# SCH_Akira_Basic_2024-01-05.net
KiCad netlist of a schematic drawn in EasyEDA
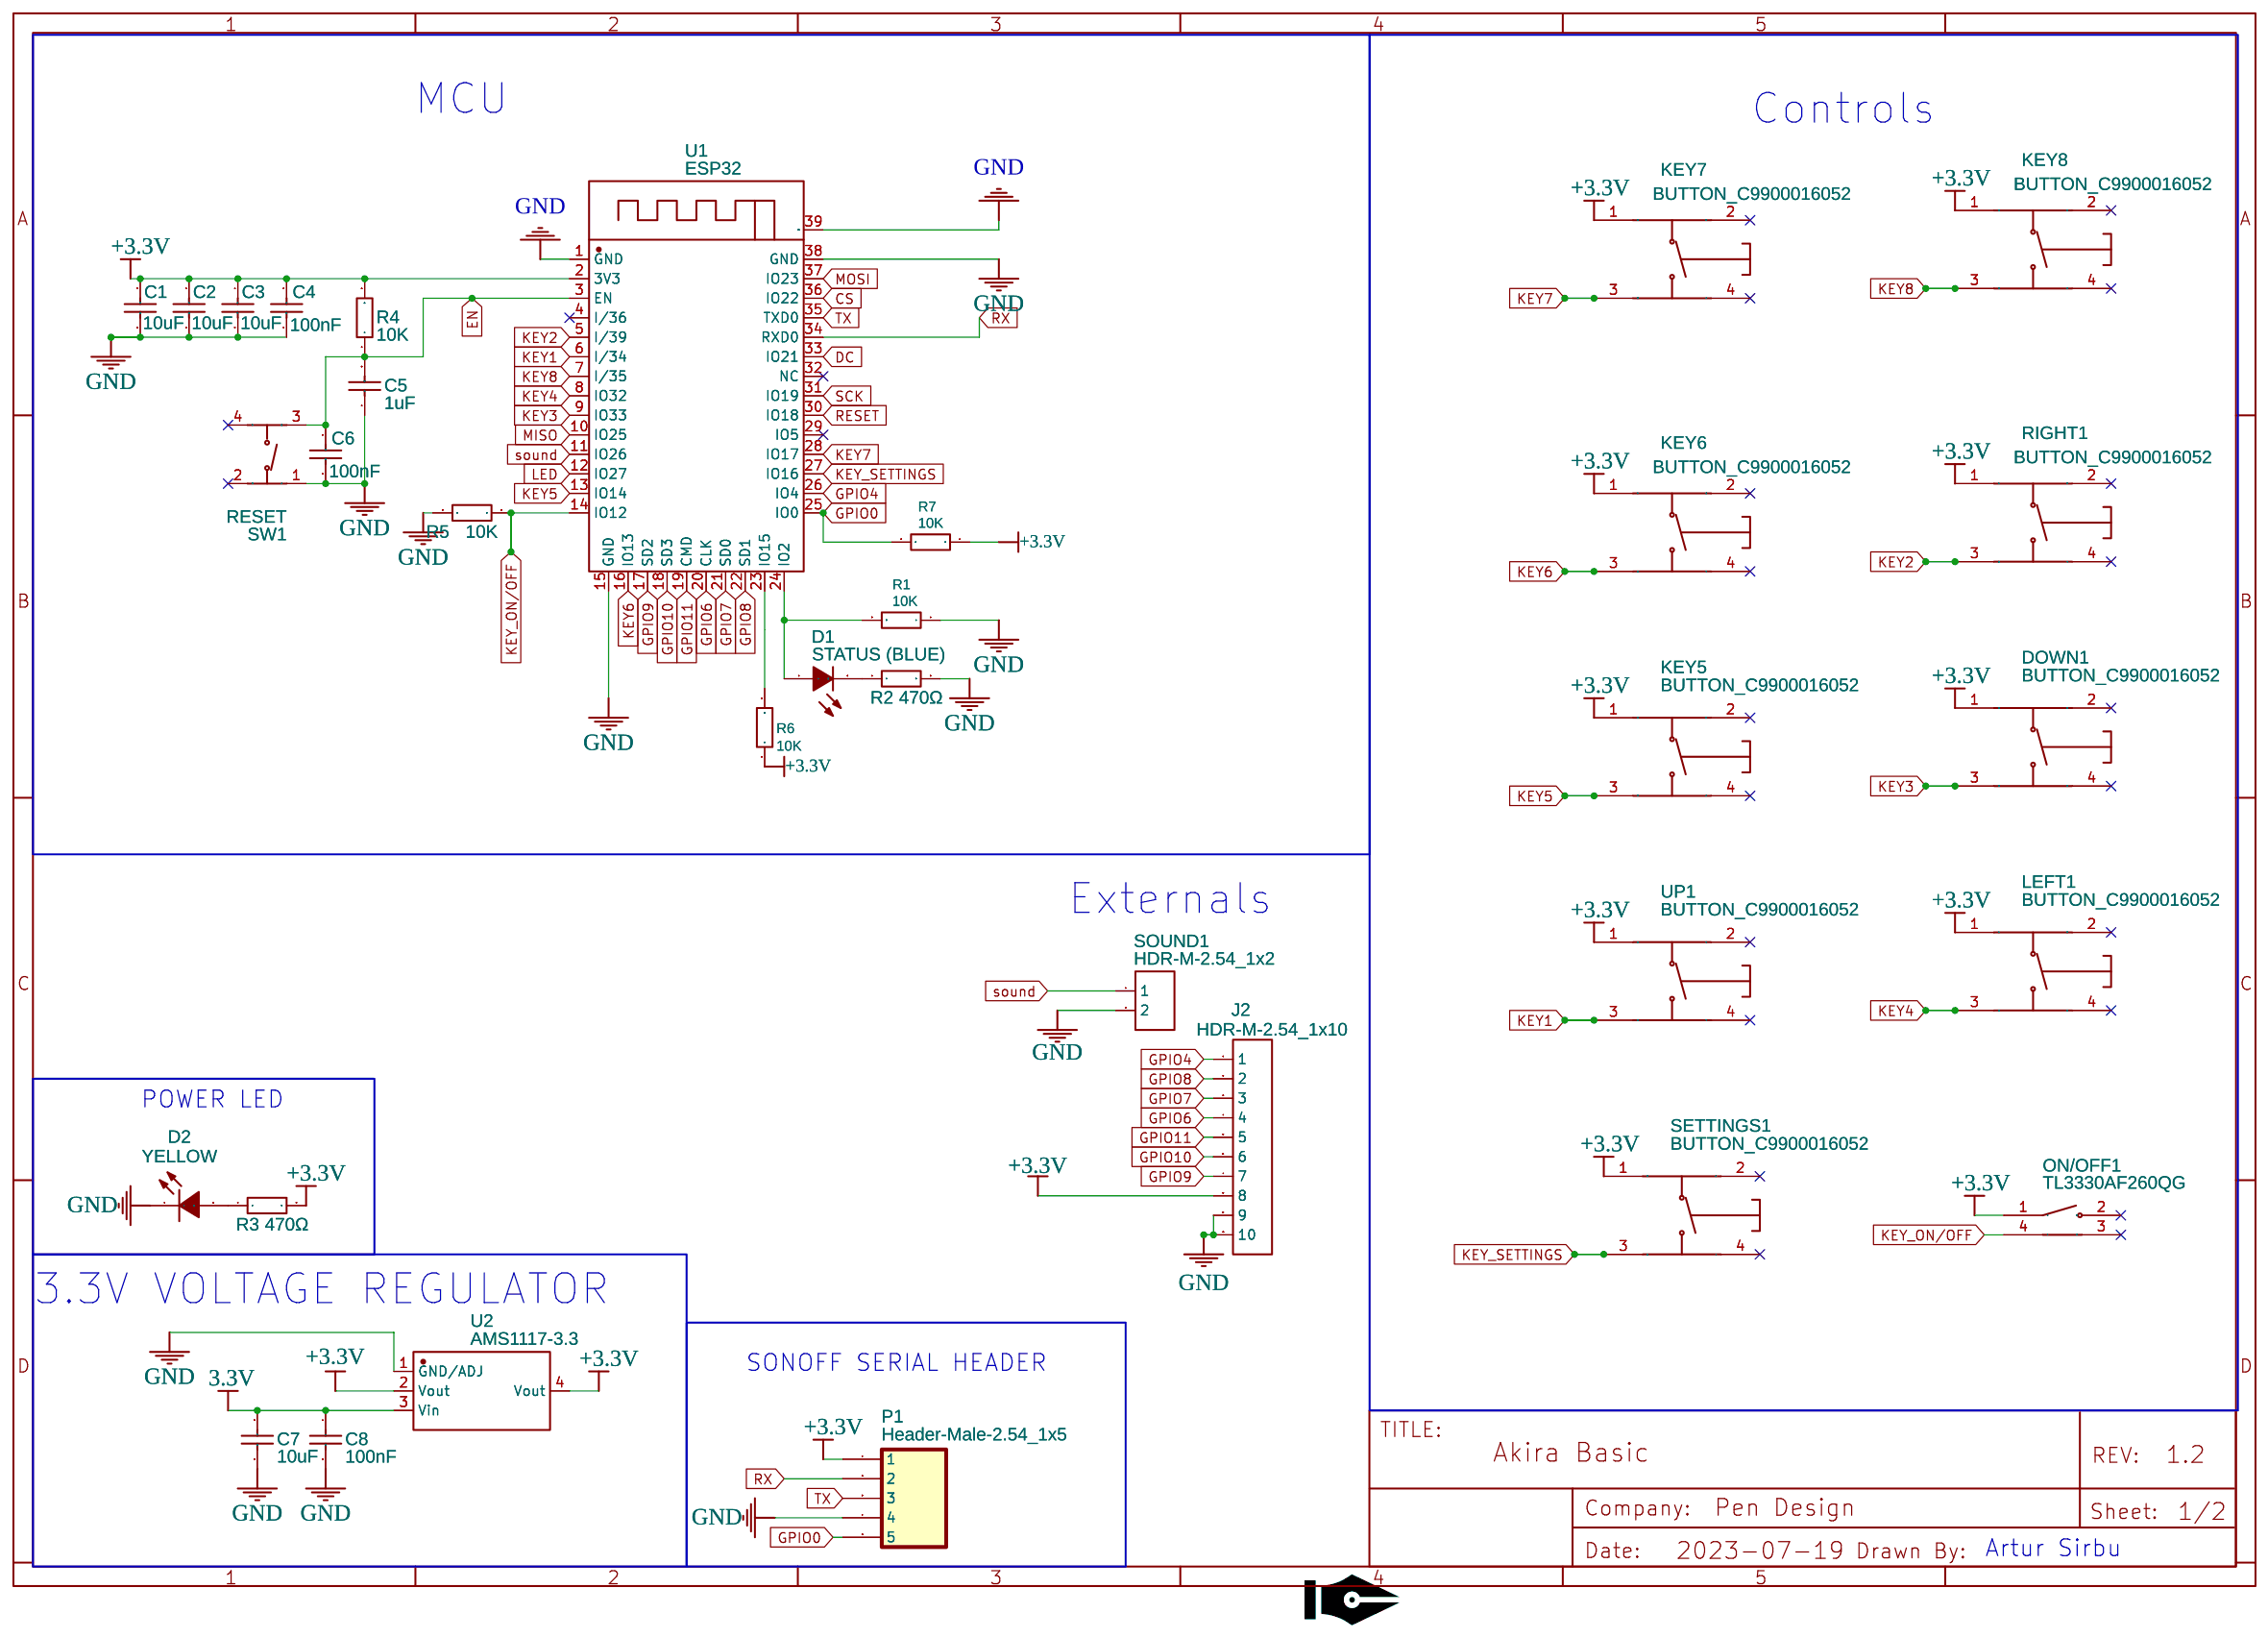
[diagram p0: Sheet_1]
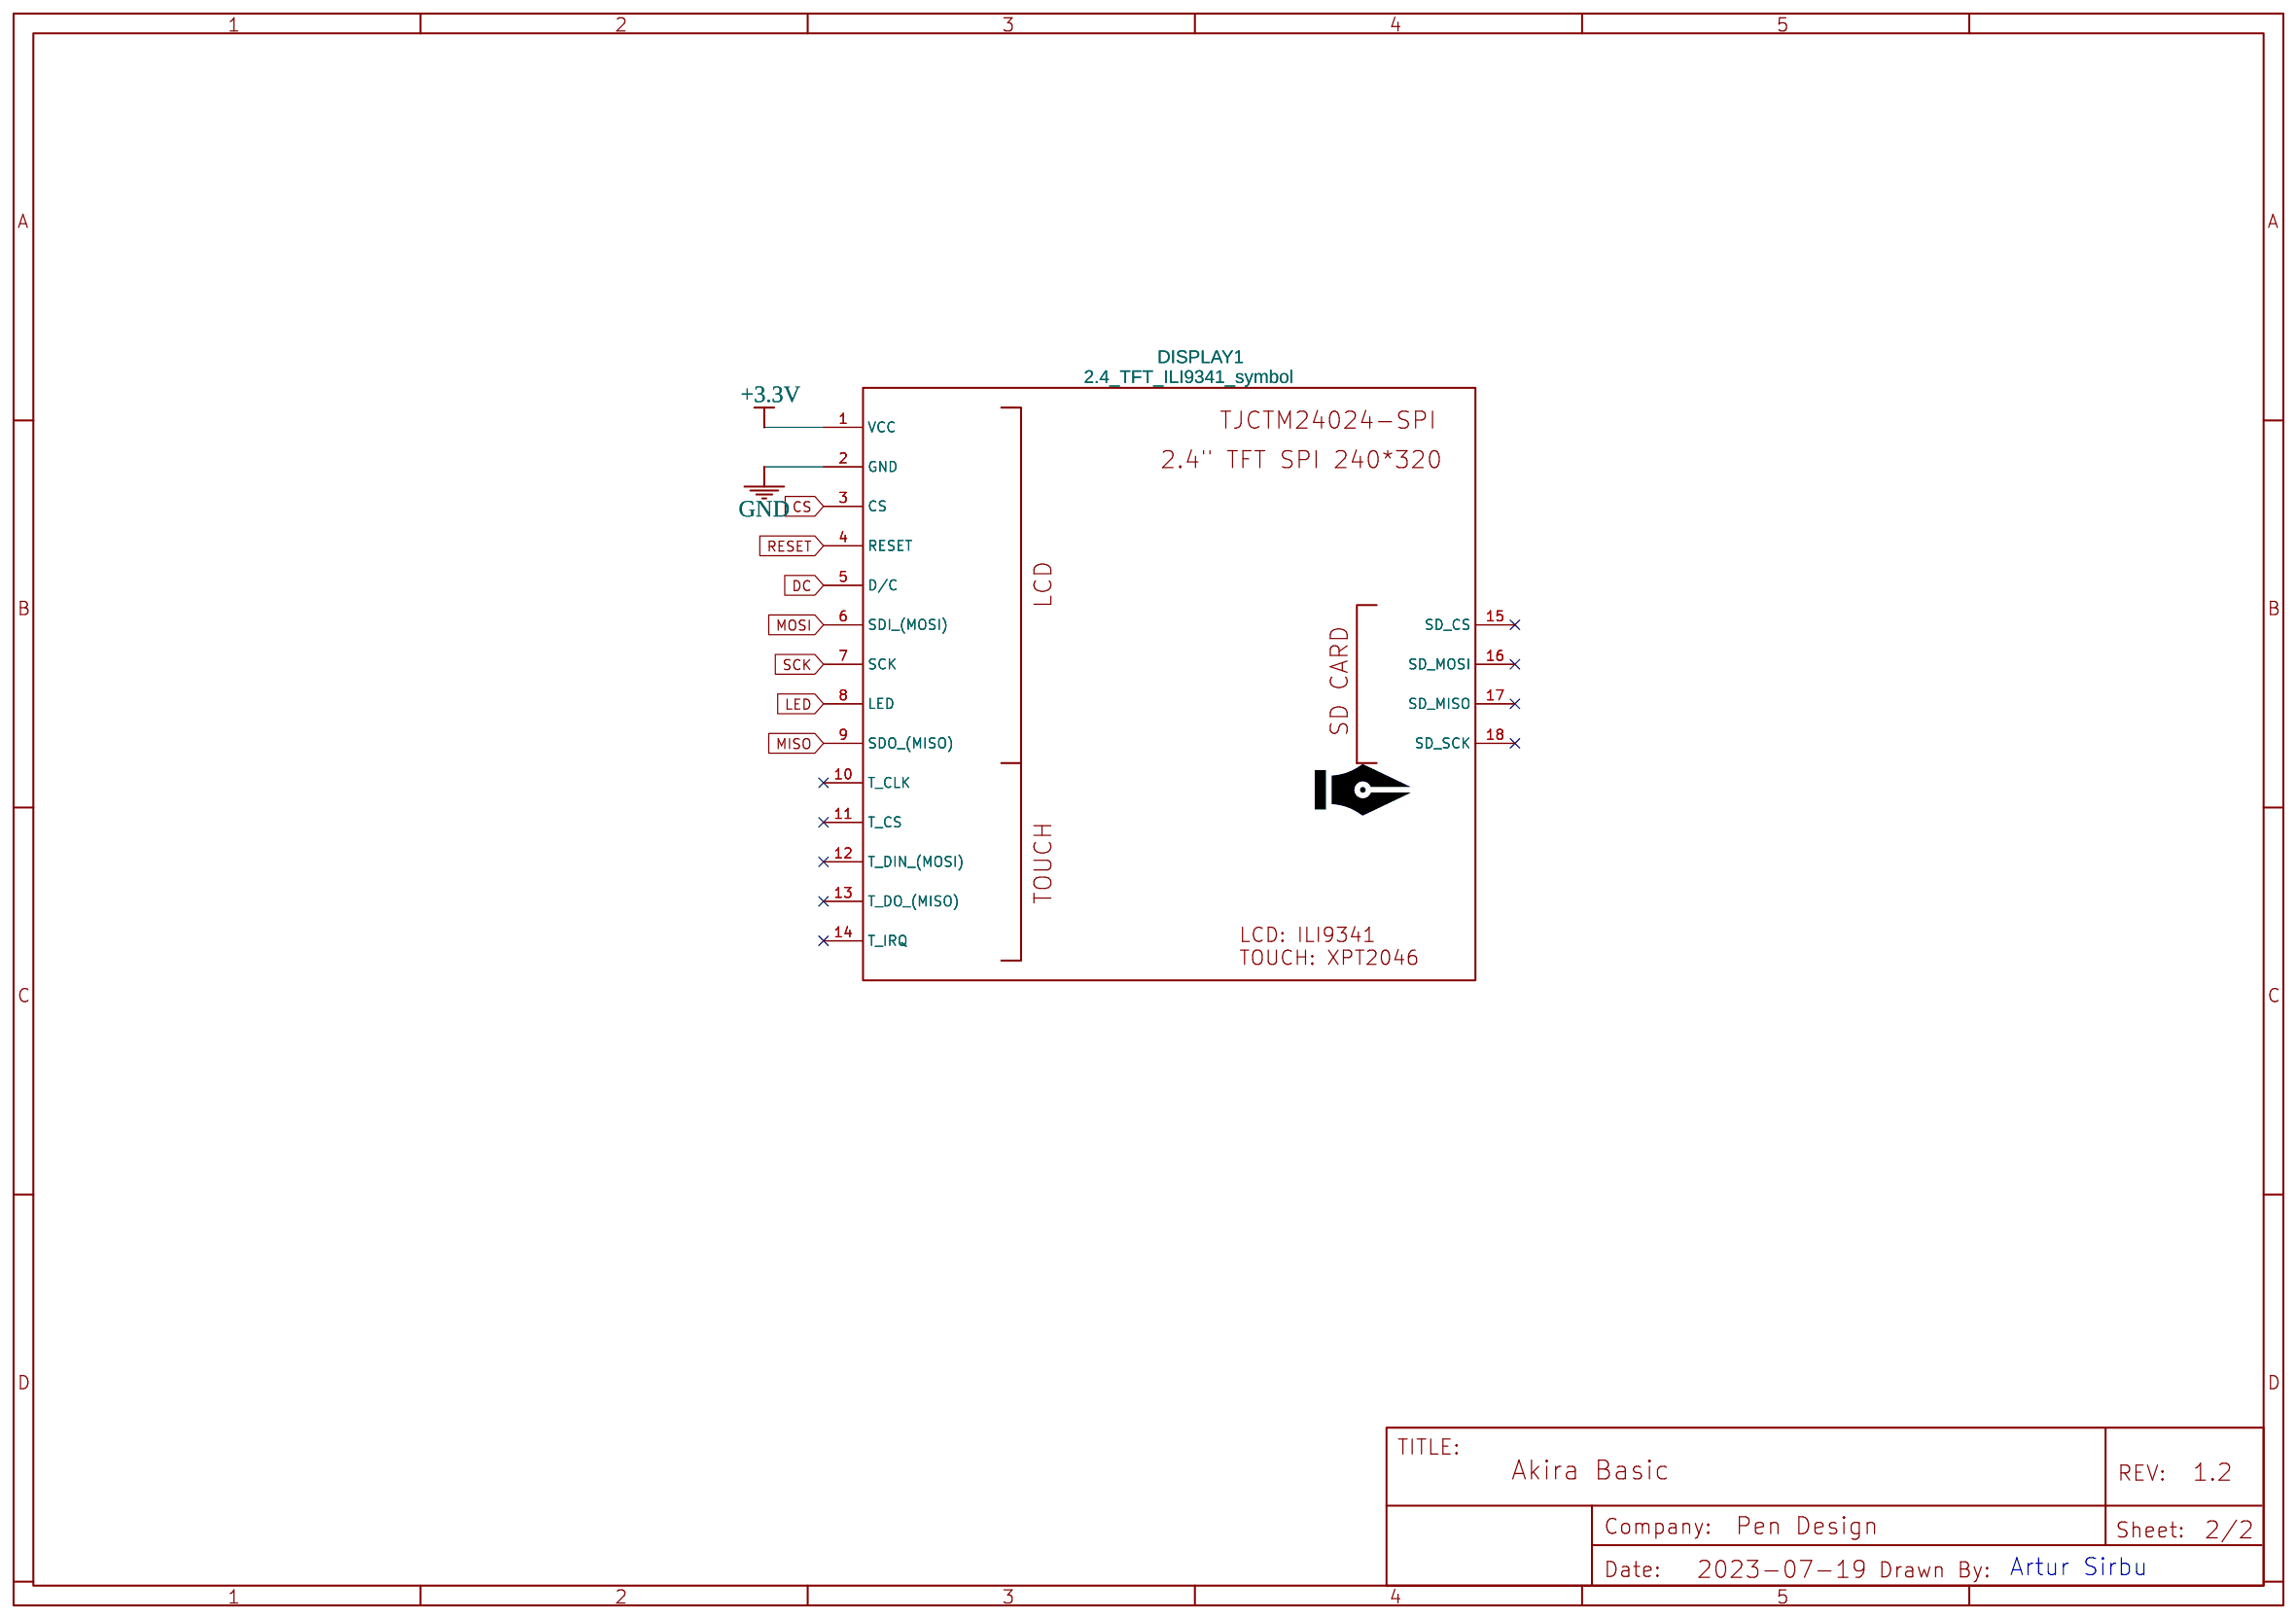
[diagram p1: Sheet_2]

(export (version "E")
  (design (tool "Eeschema 10.0.6"))
  (components
    (comp (ref "C1")
      (value "10uF")
      (fields
        (field (name "BOM_Manufacturer Part") "CL21A106KAYNNNE")
        (field (name "BOM_Supplier Part") "C15850")
      )
      (libsource (lib "") (part "CL21A106KAYNNNE"))
    )
    (comp (ref "C2")
      (value "10uF")
      (fields
        (field (name "BOM_Manufacturer Part") "CL21A106KAYNNNE")
        (field (name "BOM_Supplier Part") "C15850")
      )
      (libsource (lib "") (part "CL21A106KAYNNNE"))
    )
    (comp (ref "C3")
      (value "10uF")
      (fields
        (field (name "BOM_Manufacturer Part") "CL21A106KAYNNNE")
        (field (name "BOM_Supplier Part") "C15850")
      )
      (libsource (lib "") (part "CL21A106KAYNNNE_1"))
    )
    (comp (ref "C4")
      (value "100nF")
      (fields
        (field (name "BOM_Manufacturer Part") "CC0805KRX7R9BB104")
        (field (name "BOM_Supplier Part") "C49678")
      )
      (libsource (lib "") (part "CC0805KRX7R9BB104"))
    )
    (comp (ref "C5")
      (value "1uF")
      (fields
        (field (name "BOM_Manufacturer Part") "CL21B105KBFNNNE")
        (field (name "BOM_Supplier Part") "C28323")
      )
      (libsource (lib "") (part "CL21B105KBFNNNE"))
    )
    (comp (ref "C6")
      (value "100nF")
      (fields
        (field (name "BOM_Manufacturer Part") "CC0805KRX7R9BB104")
        (field (name "BOM_Supplier Part") "C49678")
      )
      (libsource (lib "") (part "CC0805KRX7R9BB104"))
    )
    (comp (ref "C7")
      (value "10uF")
      (fields
        (field (name "BOM_Manufacturer Part") "CL21A106KAYNNNE")
        (field (name "BOM_Supplier Part") "C15850")
      )
      (libsource (lib "") (part "CL21A106KAYNNNE"))
    )
    (comp (ref "C8")
      (value "100nF")
      (fields
        (field (name "BOM_Manufacturer Part") "CC0805KRX7R9BB104")
        (field (name "BOM_Supplier Part") "C49678")
      )
      (libsource (lib "") (part "CC0805KRX7R9BB104_1"))
    )
    (comp (ref "D1")
      (value "STATUS (BLUE)")
      (fields
        (field (name "BOM_Manufacturer Part") "19-217/BHC-ZL1M2RY/3T")
        (field (name "BOM_Supplier Part") "C72041")
      )
      (libsource (lib "") (part "19-217/BHC-ZL1M2RY/3T"))
    )
    (comp (ref "D2")
      (value "YELLOW")
      (fields
        (field (name "BOM_Manufacturer Part") "17-21SUYC/TR8")
        (field (name "BOM_Supplier Part") "C2296")
      )
      (libsource (lib "") (part "17-21SUYC/TR8"))
    )
    (comp (ref "DOWN1")
      (value "BUTTON_C9900016052")
      (fields
        (field (name "BOM_Manufacturer Part") "button")
        (field (name "BOM_Supplier Part") "C9900016052")
      )
      (libsource (lib "") (part "BUTTON_C9900016052_5"))
    )
    (comp (ref "J2")
      (value "HDR-M-2.54_1x10")
      (fields (field (name "BOM_Supplier Part") "C57369"))
      (libsource (lib "") (part "HDR-M-2.54_1x10"))
    )
    (comp (ref "KEY5")
      (value "BUTTON_C9900016052")
      (fields
        (field (name "BOM_Manufacturer Part") "button")
        (field (name "BOM_Supplier Part") "C9900016052")
      )
      (libsource (lib "") (part "BUTTON_C9900016052"))
    )
    (comp (ref "KEY6")
      (value "BUTTON_C9900016052")
      (fields
        (field (name "BOM_Manufacturer Part") "button")
        (field (name "BOM_Supplier Part") "C9900016052")
      )
      (libsource (lib "") (part "BUTTON_C9900016052"))
    )
    (comp (ref "KEY7")
      (value "BUTTON_C9900016052")
      (fields
        (field (name "BOM_Manufacturer Part") "button")
        (field (name "BOM_Supplier Part") "C9900016052")
      )
      (libsource (lib "") (part "BUTTON_C9900016052"))
    )
    (comp (ref "KEY8")
      (value "BUTTON_C9900016052")
      (fields
        (field (name "BOM_Manufacturer Part") "button")
        (field (name "BOM_Supplier Part") "C9900016052")
      )
      (libsource (lib "") (part "BUTTON_C9900016052"))
    )
    (comp (ref "LEFT1")
      (value "BUTTON_C9900016052")
      (fields
        (field (name "BOM_Manufacturer Part") "button")
        (field (name "BOM_Supplier Part") "C9900016052")
      )
      (libsource (lib "") (part "BUTTON_C9900016052_3"))
    )
    (comp (ref "ON/OFF1")
      (value "TL3330AF260QG")
      (fields (field (name "BOM_Supplier Part") "C2886886"))
      (libsource (lib "") (part "TL3330AF260QG"))
    )
    (comp (ref "P1") (value "Header-Male-2.54_1x5") (libsource (lib "") (part "Header-Male-2.54_1x5")))
    (comp (ref "R1")
      (value "10K")
      (fields
        (field (name "BOM_Manufacturer Part") "0805W8F1002T5E")
        (field (name "BOM_Supplier Part") "C17414")
      )
      (libsource (lib "") (part "0805W8F1002T5E"))
    )
    (comp (ref "R2")
      (value "470Ω")
      (fields
        (field (name "BOM_Manufacturer Part") "0805W8F4700T5E")
        (field (name "BOM_Supplier Part") "C17710")
      )
      (libsource (lib "") (part "0805W8F4700T5E"))
    )
    (comp (ref "R3")
      (value "470Ω")
      (fields
        (field (name "BOM_Manufacturer Part") "0805W8F4700T5E")
        (field (name "BOM_Supplier Part") "C17710")
      )
      (libsource (lib "") (part "0805W8F4700T5E"))
    )
    (comp (ref "R4")
      (value "10K")
      (fields
        (field (name "BOM_Manufacturer Part") "0805W8F1002T5E")
        (field (name "BOM_Supplier Part") "C17414")
      )
      (libsource (lib "") (part "0805W8F1002T5E_2"))
    )
    (comp (ref "R5")
      (value "10K")
      (fields
        (field (name "BOM_Manufacturer Part") "0805W8F1002T5E")
        (field (name "BOM_Supplier Part") "C17414")
      )
      (libsource (lib "") (part "0805W8F1002T5E_1"))
    )
    (comp (ref "R6")
      (value "10K")
      (fields
        (field (name "BOM_Manufacturer Part") "0805W8F1002T5E")
        (field (name "BOM_Supplier Part") "C17414")
      )
      (libsource (lib "") (part "0805W8F1002T5E_2"))
    )
    (comp (ref "R7")
      (value "10K")
      (fields
        (field (name "BOM_Manufacturer Part") "0805W8F1002T5E")
        (field (name "BOM_Supplier Part") "C17414")
      )
      (libsource (lib "") (part "0805W8F1002T5E"))
    )
    (comp (ref "RIGHT1")
      (value "BUTTON_C9900016052")
      (fields
        (field (name "BOM_Manufacturer Part") "button")
        (field (name "BOM_Supplier Part") "C9900016052")
      )
      (libsource (lib "") (part "BUTTON_C9900016052_1"))
    )
    (comp (ref "SETTINGS1")
      (value "BUTTON_C9900016052")
      (fields
        (field (name "BOM_Manufacturer Part") "button")
        (field (name "BOM_Supplier Part") "C9900016052")
      )
      (libsource (lib "") (part "BUTTON_C9900016052_2"))
    )
    (comp (ref "SOUND1")
      (value "HDR-M-2.54_1x2")
      (fields (field (name "BOM_Supplier Part") "C124375"))
      (libsource (lib "") (part "HDR-M-2.54_1x2"))
    )
    (comp (ref "SW1")
      (value "RESET")
      (fields
        (field (name "BOM_Manufacturer Part") "TS-1187A-B-A-B")
        (field (name "BOM_Supplier Part") "C318884")
      )
      (libsource (lib "") (part "TS-1187A-B-A-B"))
    )
    (comp (ref "U1")
      (value "ESP32")
      (fields (field (name "BOM_Supplier Part") "C328062"))
      (libsource (lib "") (part "ESP32-WROOM-32U"))
    )
    (comp (ref "U2")
      (value "AMS1117-3.3")
      (fields (field (name "BOM_Supplier Part") "C6186"))
      (libsource (lib "") (part "AMS1117-3.3"))
    )
    (comp (ref "UP1")
      (value "BUTTON_C9900016052")
      (fields
        (field (name "BOM_Manufacturer Part") "button")
        (field (name "BOM_Supplier Part") "C9900016052")
      )
      (libsource (lib "") (part "BUTTON_C9900016052_4"))
    )
    (comp (ref "DISPLAY1")
      (value "2.4_TFT_ILI9341_symbol")
      (fields (field (name "BOM_Supplier Part") "ili9341-24-touch"))
      (libsource (lib "") (part "2.4_TFT_ILI9341_symbol"))
    )
  )
  (nets
    (net (code "1") (name "+3.3V") (class "Default")
      (node (ref "C1") (pin "2") (pinfunction "2_2") (pintype "input"))
      (node (ref "C2") (pin "2") (pinfunction "2_2") (pintype "input"))
      (node (ref "C3") (pin "1") (pinfunction "1_1") (pintype "input"))
      (node (ref "C4") (pin "2") (pinfunction "2_2") (pintype "input"))
      (node (ref "DISPLAY1") (pin "1") (pinfunction "VCC_1") (pintype "unspecified"))
      (node (ref "DOWN1") (pin "1") (pinfunction "1_1") (pintype "unspecified"))
      (node (ref "J2") (pin "8") (pinfunction "8_8") (pintype "unspecified"))
      (node (ref "KEY5") (pin "1") (pinfunction "1_1") (pintype "unspecified"))
      (node (ref "KEY6") (pin "1") (pinfunction "1_1") (pintype "unspecified"))
      (node (ref "KEY7") (pin "1") (pinfunction "1_1") (pintype "unspecified"))
      (node (ref "KEY8") (pin "1") (pinfunction "1_1") (pintype "unspecified"))
      (node (ref "LEFT1") (pin "1") (pinfunction "1_1") (pintype "unspecified"))
      (node (ref "ON/OFF1") (pin "1") (pinfunction "1_1") (pintype "unspecified"))
      (node (ref "P1") (pin "1") (pinfunction "1_1") (pintype "input"))
      (node (ref "R3") (pin "2") (pinfunction "2_2") (pintype "input"))
      (node (ref "R4") (pin "2") (pinfunction "2_2") (pintype "input"))
      (node (ref "R6") (pin "1") (pinfunction "1_1") (pintype "input"))
      (node (ref "R7") (pin "1") (pinfunction "1_1") (pintype "input"))
      (node (ref "RIGHT1") (pin "1") (pinfunction "1_1") (pintype "unspecified"))
      (node (ref "SETTINGS1") (pin "1") (pinfunction "1_1") (pintype "unspecified"))
      (node (ref "U1") (pin "2") (pinfunction "3V3_2") (pintype "unspecified"))
      (node (ref "U2") (pin "2") (pinfunction "Vout_2") (pintype "unspecified"))
      (node (ref "U2") (pin "4") (pinfunction "Vout_4") (pintype "unspecified"))
      (node (ref "UP1") (pin "1") (pinfunction "1_1") (pintype "unspecified"))
    )
    (net (code "2") (name "3.3V") (class "Default")
      (node (ref "C7") (pin "2") (pinfunction "2_2") (pintype "input"))
      (node (ref "C8") (pin "1") (pinfunction "1_1") (pintype "input"))
      (node (ref "U2") (pin "3") (pinfunction "Vin_3") (pintype "unspecified"))
    )
    (net (code "3") (name "CS") (class "Default")
      (node (ref "DISPLAY1") (pin "3") (pinfunction "CS_3") (pintype "unspecified"))
      (node (ref "U1") (pin "36") (pinfunction "IO22_36") (pintype "unspecified"))
    )
    (net (code "4") (name "DC") (class "Default")
      (node (ref "DISPLAY1") (pin "5") (pinfunction "D/C_5") (pintype "unspecified"))
      (node (ref "U1") (pin "33") (pinfunction "IO21_33") (pintype "unspecified"))
    )
    (net (code "5") (name "EN") (class "Default")
      (node (ref "C5") (pin "2") (pinfunction "2_2") (pintype "input"))
      (node (ref "C6") (pin "2") (pinfunction "2_2") (pintype "input"))
      (node (ref "R4") (pin "1") (pinfunction "1_1") (pintype "input"))
      (node (ref "SW1") (pin "3") (pinfunction "C_3") (pintype "unspecified"))
      (node (ref "U1") (pin "3") (pinfunction "EN_3") (pintype "unspecified"))
    )
    (net (code "6") (name "GND") (class "Default")
      (node (ref "C1") (pin "1") (pinfunction "1_1") (pintype "input"))
      (node (ref "C2") (pin "1") (pinfunction "1_1") (pintype "input"))
      (node (ref "C3") (pin "2") (pinfunction "2_2") (pintype "input"))
      (node (ref "C4") (pin "1") (pinfunction "1_1") (pintype "input"))
      (node (ref "C5") (pin "1") (pinfunction "1_1") (pintype "input"))
      (node (ref "C6") (pin "1") (pinfunction "1_1") (pintype "input"))
      (node (ref "C7") (pin "1") (pinfunction "1_1") (pintype "input"))
      (node (ref "C8") (pin "2") (pinfunction "2_2") (pintype "input"))
      (node (ref "D2") (pin "1") (pinfunction "-_1") (pintype "unspecified"))
      (node (ref "DISPLAY1") (pin "2") (pinfunction "GND_2") (pintype "unspecified"))
      (node (ref "J2") (pin "10") (pinfunction "10_10") (pintype "unspecified"))
      (node (ref "J2") (pin "9") (pinfunction "9_9") (pintype "unspecified"))
      (node (ref "P1") (pin "4") (pinfunction "4_4") (pintype "input"))
      (node (ref "R1") (pin "1") (pinfunction "1_1") (pintype "input"))
      (node (ref "R2") (pin "2") (pinfunction "2_2") (pintype "input"))
      (node (ref "R5") (pin "1") (pinfunction "1_1") (pintype "input"))
      (node (ref "SOUND1") (pin "2") (pinfunction "2_2") (pintype "unspecified"))
      (node (ref "SW1") (pin "1") (pinfunction "A_1") (pintype "unspecified"))
      (node (ref "U1") (pin "1") (pinfunction "GND_1") (pintype "unspecified"))
      (node (ref "U1") (pin "15") (pinfunction "GND_15") (pintype "unspecified"))
      (node (ref "U1") (pin "38") (pinfunction "GND_38") (pintype "unspecified"))
      (node (ref "U1") (pin "39") (pinfunction "GND_39") (pintype "unspecified"))
      (node (ref "U2") (pin "1") (pinfunction "GND/ADJ_1") (pintype "unspecified"))
    )
    (net (code "7") (name "GPIO0") (class "Default")
      (node (ref "P1") (pin "5") (pinfunction "5_5") (pintype "input"))
      (node (ref "R7") (pin "2") (pinfunction "2_2") (pintype "input"))
      (node (ref "U1") (pin "25") (pinfunction "IO0_25") (pintype "unspecified"))
    )
    (net (code "8") (name "GPIO4") (class "Default")
      (node (ref "J2") (pin "1") (pinfunction "1_1") (pintype "unspecified"))
      (node (ref "U1") (pin "26") (pinfunction "IO4_26") (pintype "unspecified"))
    )
    (net (code "9") (name "GPIO6") (class "Default")
      (node (ref "J2") (pin "4") (pinfunction "4_4") (pintype "unspecified"))
      (node (ref "U1") (pin "20") (pinfunction "CLK_20") (pintype "unspecified"))
    )
    (net (code "10") (name "GPIO7") (class "Default")
      (node (ref "J2") (pin "3") (pinfunction "3_3") (pintype "unspecified"))
      (node (ref "U1") (pin "21") (pinfunction "SD0_21") (pintype "unspecified"))
    )
    (net (code "11") (name "GPIO8") (class "Default")
      (node (ref "J2") (pin "2") (pinfunction "2_2") (pintype "unspecified"))
      (node (ref "U1") (pin "22") (pinfunction "SD1_22") (pintype "unspecified"))
    )
    (net (code "12") (name "GPIO9") (class "Default")
      (node (ref "J2") (pin "7") (pinfunction "7_7") (pintype "unspecified"))
      (node (ref "U1") (pin "17") (pinfunction "SD2_17") (pintype "unspecified"))
    )
    (net (code "13") (name "GPIO10") (class "Default")
      (node (ref "J2") (pin "6") (pinfunction "6_6") (pintype "unspecified"))
      (node (ref "U1") (pin "18") (pinfunction "SD3_18") (pintype "unspecified"))
    )
    (net (code "14") (name "GPIO11") (class "Default")
      (node (ref "J2") (pin "5") (pinfunction "5_5") (pintype "unspecified"))
      (node (ref "U1") (pin "19") (pinfunction "CMD_19") (pintype "unspecified"))
    )
    (net (code "15") (name "KEY1") (class "Default")
      (node (ref "U1") (pin "6") (pinfunction "I/34_6") (pintype "unspecified"))
      (node (ref "UP1") (pin "3") (pinfunction "3_3") (pintype "unspecified"))
    )
    (net (code "16") (name "KEY2") (class "Default")
      (node (ref "RIGHT1") (pin "3") (pinfunction "3_3") (pintype "unspecified"))
      (node (ref "U1") (pin "5") (pinfunction "I/39_5") (pintype "unspecified"))
    )
    (net (code "17") (name "KEY3") (class "Default")
      (node (ref "DOWN1") (pin "3") (pinfunction "3_3") (pintype "unspecified"))
      (node (ref "U1") (pin "9") (pinfunction "IO33_9") (pintype "unspecified"))
    )
    (net (code "18") (name "KEY4") (class "Default")
      (node (ref "LEFT1") (pin "3") (pinfunction "3_3") (pintype "unspecified"))
      (node (ref "U1") (pin "8") (pinfunction "IO32_8") (pintype "unspecified"))
    )
    (net (code "19") (name "KEY5") (class "Default")
      (node (ref "KEY5") (pin "3") (pinfunction "3_3") (pintype "unspecified"))
      (node (ref "U1") (pin "13") (pinfunction "IO14_13") (pintype "unspecified"))
    )
    (net (code "20") (name "KEY6") (class "Default")
      (node (ref "KEY6") (pin "3") (pinfunction "3_3") (pintype "unspecified"))
      (node (ref "U1") (pin "16") (pinfunction "IO13_16") (pintype "unspecified"))
    )
    (net (code "21") (name "KEY7") (class "Default")
      (node (ref "KEY7") (pin "3") (pinfunction "3_3") (pintype "unspecified"))
      (node (ref "U1") (pin "28") (pinfunction "IO17_28") (pintype "unspecified"))
    )
    (net (code "22") (name "KEY8") (class "Default")
      (node (ref "KEY8") (pin "3") (pinfunction "3_3") (pintype "unspecified"))
      (node (ref "U1") (pin "7") (pinfunction "I/35_7") (pintype "unspecified"))
    )
    (net (code "23") (name "KEY_ON{slash}OFF") (class "Default")
      (node (ref "ON/OFF1") (pin "4") (pinfunction "4_4") (pintype "unspecified"))
      (node (ref "R5") (pin "2") (pinfunction "2_2") (pintype "input"))
      (node (ref "U1") (pin "14") (pinfunction "IO12_14") (pintype "unspecified"))
    )
    (net (code "24") (name "KEY_SETTINGS") (class "Default")
      (node (ref "SETTINGS1") (pin "3") (pinfunction "3_3") (pintype "unspecified"))
      (node (ref "U1") (pin "27") (pinfunction "IO16_27") (pintype "unspecified"))
    )
    (net (code "25") (name "LED") (class "Default")
      (node (ref "DISPLAY1") (pin "8") (pinfunction "LED_8") (pintype "unspecified"))
      (node (ref "U1") (pin "12") (pinfunction "IO27_12") (pintype "unspecified"))
    )
    (net (code "26") (name "MISO") (class "Default")
      (node (ref "DISPLAY1") (pin "9") (pinfunction "SDO_(MISO)_9") (pintype "unspecified"))
      (node (ref "U1") (pin "10") (pinfunction "IO25_10") (pintype "unspecified"))
    )
    (net (code "27") (name "MOSI") (class "Default")
      (node (ref "DISPLAY1") (pin "6") (pinfunction "SDI_(MOSI)_6") (pintype "unspecified"))
      (node (ref "U1") (pin "37") (pinfunction "IO23_37") (pintype "unspecified"))
    )
    (net (code "28") (name "Net-(D1-A)") (class "Default")
      (node (ref "D1") (pin "1") (pinfunction "A_1") (pintype "input"))
      (node (ref "R1") (pin "2") (pinfunction "2_2") (pintype "input"))
      (node (ref "U1") (pin "24") (pinfunction "IO2_24") (pintype "unspecified"))
    )
    (net (code "29") (name "Net-(D1-C)") (class "Default")
      (node (ref "D1") (pin "2") (pinfunction "C_2") (pintype "input"))
      (node (ref "R2") (pin "1") (pinfunction "1_1") (pintype "input"))
    )
    (net (code "30") (name "Net-(D2-+)") (class "Default")
      (node (ref "D2") (pin "2") (pinfunction "+_2") (pintype "unspecified"))
      (node (ref "R3") (pin "1") (pinfunction "1_1") (pintype "input"))
    )
    (net (code "31") (name "Net-(U1-IO15)") (class "Default")
      (node (ref "R6") (pin "2") (pinfunction "2_2") (pintype "input"))
      (node (ref "U1") (pin "23") (pinfunction "IO15_23") (pintype "unspecified"))
    )
    (net (code "32") (name "RESET") (class "Default")
      (node (ref "DISPLAY1") (pin "4") (pinfunction "RESET_4") (pintype "unspecified"))
      (node (ref "U1") (pin "30") (pinfunction "IO18_30") (pintype "unspecified"))
    )
    (net (code "33") (name "RX") (class "Default")
      (node (ref "P1") (pin "2") (pinfunction "2_2") (pintype "input"))
      (node (ref "U1") (pin "34") (pinfunction "RXD0_34") (pintype "unspecified"))
    )
    (net (code "34") (name "SCK") (class "Default")
      (node (ref "DISPLAY1") (pin "7") (pinfunction "SCK_7") (pintype "unspecified"))
      (node (ref "U1") (pin "31") (pinfunction "IO19_31") (pintype "unspecified"))
    )
    (net (code "35") (name "TX") (class "Default")
      (node (ref "P1") (pin "3") (pinfunction "3_3") (pintype "input"))
      (node (ref "U1") (pin "35") (pinfunction "TXD0_35") (pintype "unspecified"))
    )
    (net (code "36") (name "sound") (class "Default")
      (node (ref "SOUND1") (pin "1") (pinfunction "1_1") (pintype "unspecified"))
      (node (ref "U1") (pin "11") (pinfunction "IO26_11") (pintype "unspecified"))
    )
    (net (code "37") (name "unconnected-(DISPLAY1-SD_CS-Pad15)") (class "Default")
      (node (ref "DISPLAY1") (pin "15") (pinfunction "SD_CS_15") (pintype "unspecified+no_connect"))
    )
    (net (code "38") (name "unconnected-(DISPLAY1-SD_MISO-Pad17)") (class "Default")
      (node (ref "DISPLAY1") (pin "17") (pinfunction "SD_MISO_17") (pintype "unspecified+no_connect"))
    )
    (net (code "39") (name "unconnected-(DISPLAY1-SD_MOSI-Pad16)") (class "Default")
      (node (ref "DISPLAY1") (pin "16") (pinfunction "SD_MOSI_16") (pintype "unspecified+no_connect"))
    )
    (net (code "40") (name "unconnected-(DISPLAY1-SD_SCK-Pad18)") (class "Default")
      (node (ref "DISPLAY1") (pin "18") (pinfunction "SD_SCK_18") (pintype "unspecified+no_connect"))
    )
    (net (code "41") (name "unconnected-(DISPLAY1-T_CLK-Pad10)") (class "Default")
      (node (ref "DISPLAY1") (pin "10") (pinfunction "T_CLK_10") (pintype "unspecified+no_connect"))
    )
    (net (code "42") (name "unconnected-(DISPLAY1-T_CS-Pad11)") (class "Default")
      (node (ref "DISPLAY1") (pin "11") (pinfunction "T_CS_11") (pintype "unspecified+no_connect"))
    )
    (net (code "43") (name "unconnected-(DISPLAY1-T_DIN_(MOSI)-Pad12)") (class "Default")
      (node (ref "DISPLAY1") (pin "12") (pinfunction "T_DIN_(MOSI)_12") (pintype "unspecified+no_connect"))
    )
    (net (code "44") (name "unconnected-(DISPLAY1-T_DO_(MISO)-Pad13)") (class "Default")
      (node (ref "DISPLAY1") (pin "13") (pinfunction "T_DO_(MISO)_13") (pintype "unspecified+no_connect"))
    )
    (net (code "45") (name "unconnected-(DISPLAY1-T_IRQ-Pad14)") (class "Default")
      (node (ref "DISPLAY1") (pin "14") (pinfunction "T_IRQ_14") (pintype "unspecified+no_connect"))
    )
    (net (code "46") (name "unconnected-(DOWN1-Pad2)") (class "Default")
      (node (ref "DOWN1") (pin "2") (pinfunction "2_2") (pintype "unspecified+no_connect"))
    )
    (net (code "47") (name "unconnected-(DOWN1-Pad4)") (class "Default")
      (node (ref "DOWN1") (pin "4") (pinfunction "4_4") (pintype "unspecified+no_connect"))
    )
    (net (code "48") (name "unconnected-(KEY5-Pad2)") (class "Default")
      (node (ref "KEY5") (pin "2") (pinfunction "2_2") (pintype "unspecified+no_connect"))
    )
    (net (code "49") (name "unconnected-(KEY5-Pad4)") (class "Default")
      (node (ref "KEY5") (pin "4") (pinfunction "4_4") (pintype "unspecified+no_connect"))
    )
    (net (code "50") (name "unconnected-(KEY6-Pad2)") (class "Default")
      (node (ref "KEY6") (pin "2") (pinfunction "2_2") (pintype "unspecified+no_connect"))
    )
    (net (code "51") (name "unconnected-(KEY6-Pad4)") (class "Default")
      (node (ref "KEY6") (pin "4") (pinfunction "4_4") (pintype "unspecified+no_connect"))
    )
    (net (code "52") (name "unconnected-(KEY7-Pad2)") (class "Default")
      (node (ref "KEY7") (pin "2") (pinfunction "2_2") (pintype "unspecified+no_connect"))
    )
    (net (code "53") (name "unconnected-(KEY7-Pad4)") (class "Default")
      (node (ref "KEY7") (pin "4") (pinfunction "4_4") (pintype "unspecified+no_connect"))
    )
    (net (code "54") (name "unconnected-(KEY8-Pad2)") (class "Default")
      (node (ref "KEY8") (pin "2") (pinfunction "2_2") (pintype "unspecified+no_connect"))
    )
    (net (code "55") (name "unconnected-(KEY8-Pad4)") (class "Default")
      (node (ref "KEY8") (pin "4") (pinfunction "4_4") (pintype "unspecified+no_connect"))
    )
    (net (code "56") (name "unconnected-(LEFT1-Pad2)") (class "Default")
      (node (ref "LEFT1") (pin "2") (pinfunction "2_2") (pintype "unspecified+no_connect"))
    )
    (net (code "57") (name "unconnected-(LEFT1-Pad4)") (class "Default")
      (node (ref "LEFT1") (pin "4") (pinfunction "4_4") (pintype "unspecified+no_connect"))
    )
    (net (code "58") (name "unconnected-(ON/OFF1-Pad2)") (class "Default")
      (node (ref "ON/OFF1") (pin "2") (pinfunction "2_2") (pintype "unspecified+no_connect"))
    )
    (net (code "59") (name "unconnected-(ON/OFF1-Pad3)") (class "Default")
      (node (ref "ON/OFF1") (pin "3") (pinfunction "3_3") (pintype "unspecified+no_connect"))
    )
    (net (code "60") (name "unconnected-(RIGHT1-Pad2)") (class "Default")
      (node (ref "RIGHT1") (pin "2") (pinfunction "2_2") (pintype "unspecified+no_connect"))
    )
    (net (code "61") (name "unconnected-(RIGHT1-Pad4)") (class "Default")
      (node (ref "RIGHT1") (pin "4") (pinfunction "4_4") (pintype "unspecified+no_connect"))
    )
    (net (code "62") (name "unconnected-(SETTINGS1-Pad2)") (class "Default")
      (node (ref "SETTINGS1") (pin "2") (pinfunction "2_2") (pintype "unspecified+no_connect"))
    )
    (net (code "63") (name "unconnected-(SETTINGS1-Pad4)") (class "Default")
      (node (ref "SETTINGS1") (pin "4") (pinfunction "4_4") (pintype "unspecified+no_connect"))
    )
    (net (code "64") (name "unconnected-(SW1-B-Pad2)") (class "Default")
      (node (ref "SW1") (pin "2") (pinfunction "B_2") (pintype "unspecified+no_connect"))
    )
    (net (code "65") (name "unconnected-(SW1-D-Pad4)") (class "Default")
      (node (ref "SW1") (pin "4") (pinfunction "D_4") (pintype "unspecified+no_connect"))
    )
    (net (code "66") (name "unconnected-(U1-IO5-Pad29)") (class "Default")
      (node (ref "U1") (pin "29") (pinfunction "IO5_29") (pintype "unspecified+no_connect"))
    )
    (net (code "67") (name "unconnected-(U1-I{slash}36-Pad4)") (class "Default")
      (node (ref "U1") (pin "4") (pinfunction "I/36_4") (pintype "unspecified+no_connect"))
    )
    (net (code "68") (name "unconnected-(U1-NC-Pad32)") (class "Default")
      (node (ref "U1") (pin "32") (pinfunction "NC_32") (pintype "unspecified+no_connect"))
    )
    (net (code "69") (name "unconnected-(UP1-Pad2)") (class "Default")
      (node (ref "UP1") (pin "2") (pinfunction "2_2") (pintype "unspecified+no_connect"))
    )
    (net (code "70") (name "unconnected-(UP1-Pad4)") (class "Default")
      (node (ref "UP1") (pin "4") (pinfunction "4_4") (pintype "unspecified+no_connect"))
    )
  )
)
